# pilote.net
KiCad netlist of a schematic drawn in EAGLE
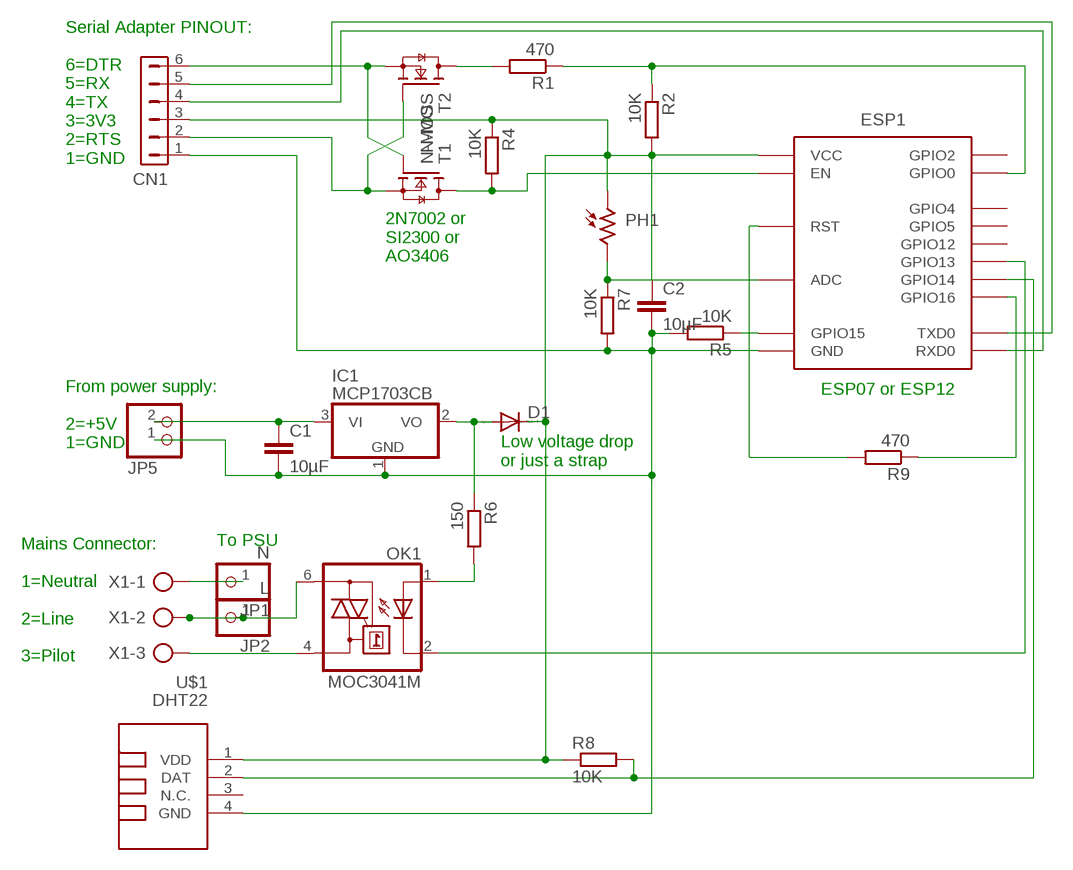
[diagram p0: schematic, sheet 1]

(export (version "E")
  (design (tool "Eeschema 10.0.6"))
  (components
    (comp (ref "C1")
      (value "10µF")
      (footprint "eagle-import:C1210")
      (libsource (lib "eagle-import") (part "C-EUC1210"))
    )
    (comp (ref "C2")
      (value "10µF")
      (footprint "eagle-import:C1210")
      (libsource (lib "eagle-import") (part "C-EUC1210"))
    )
    (comp (ref "CN1")
      (value "HDR-1X6-SIP-100")
      (footprint "eagle-import:SIP-100-6V")
      (libsource (lib "eagle-import") (part "HDR-1X6-SIP-100"))
    )
    (comp (ref "D1")
      (value "DIODE-SOD123")
      (footprint "eagle-import:SOD123")
      (libsource (lib "eagle-import") (part "DIODE-SOD123"))
    )
    (comp (ref "ESP1")
      (value "ESP8266-07THT")
      (footprint "eagle-import:ESP-07")
      (libsource (lib "eagle-import") (part "ESP8266-07THT"))
    )
    (comp (ref "IC1")
      (value "MCP1703CB")
      (footprint "eagle-import:SOT23")
      (libsource (lib "eagle-import") (part "MCP1703CB"))
    )
    (comp (ref "JP1")
      (value "N")
      (footprint "eagle-import:1X01")
      (libsource (lib "eagle-import") (part "PINHD-1X1"))
    )
    (comp (ref "JP2")
      (value "L")
      (footprint "eagle-import:1X01")
      (libsource (lib "eagle-import") (part "PINHD-1X1"))
    )
    (comp (ref "JP5")
      (value "PINHD-1X2")
      (footprint "eagle-import:1X02")
      (libsource (lib "eagle-import") (part "PINHD-1X2"))
    )
    (comp (ref "OK1")
      (value "MOC3041M")
      (footprint "eagle-import:DIL06")
      (libsource (lib "eagle-import") (part "MOC3041M"))
    )
    (comp (ref "PH1")
      (value "A1050_09")
      (footprint "eagle-import:T0-46-A10XX")
      (libsource (lib "eagle-import") (part "A1050_09"))
    )
    (comp (ref "R1")
      (value "470")
      (footprint "eagle-import:M0805")
      (libsource (lib "eagle-import") (part "R-EU_M0805"))
    )
    (comp (ref "R2")
      (value "10K")
      (footprint "eagle-import:M0805")
      (libsource (lib "eagle-import") (part "R-EU_M0805"))
    )
    (comp (ref "R4")
      (value "10K")
      (footprint "eagle-import:M0805")
      (libsource (lib "eagle-import") (part "R-EU_M0805"))
    )
    (comp (ref "R5")
      (value "10K")
      (footprint "eagle-import:M0805")
      (libsource (lib "eagle-import") (part "R-EU_M0805"))
    )
    (comp (ref "R6")
      (value "150")
      (footprint "eagle-import:M0805")
      (libsource (lib "eagle-import") (part "R-EU_M0805"))
    )
    (comp (ref "R7")
      (value "10K")
      (footprint "eagle-import:M0805")
      (libsource (lib "eagle-import") (part "R-EU_M0805"))
    )
    (comp (ref "R8")
      (value "10K")
      (footprint "eagle-import:M0805")
      (libsource (lib "eagle-import") (part "R-EU_M0805"))
    )
    (comp (ref "R9")
      (value "470")
      (footprint "eagle-import:M0805")
      (libsource (lib "eagle-import") (part "R-EU_M0805"))
    )
    (comp (ref "T1")
      (value "N-MOS")
      (footprint "eagle-import:SOT23")
      (libsource (lib "eagle-import") (part "2N7002E"))
    )
    (comp (ref "T2")
      (value "N-MOS")
      (footprint "eagle-import:SOT23")
      (libsource (lib "eagle-import") (part "2N7002E"))
    )
    (comp (ref "U$1")
      (value "DHT22")
      (footprint "eagle-import:TEMP-HUM-SENSOR-DHT22")
      (libsource (lib "eagle-import") (part "TEMP-HUM-SENSOR-DHT22"))
    )
    (comp (ref "X1")
      (value "AK500/3")
      (footprint "eagle-import:AK500_3")
      (libsource (lib "eagle-import") (part "AK500/3"))
    )
  )
  (nets
    (net (code "1") (name "Net-(ESP1-PadADC)") (class "Default")
      (node (ref "ESP1") (pin "ADC") (pinfunction "ADC_ADC") (pintype "input"))
      (node (ref "PH1") (pin "2") (pinfunction "2_2") (pintype "passive"))
      (node (ref "R7") (pin "1") (pinfunction "1_1") (pintype "passive"))
    )
    (net (code "2") (name "Net-(ESP1-PadGPIO0)") (class "Default")
      (node (ref "ESP1") (pin "GPIO0") (pinfunction "GPIO0_GPIO0") (pintype "bidirectional"))
      (node (ref "R1") (pin "1") (pinfunction "1_1") (pintype "passive"))
      (node (ref "R2") (pin "1") (pinfunction "1_1") (pintype "passive"))
    )
    (net (code "3") (name "Net-(ESP1-PadGPIO15)") (class "Default")
      (node (ref "ESP1") (pin "GPIO15") (pinfunction "GPIO15_GPIO15") (pintype "bidirectional"))
      (node (ref "R5") (pin "1") (pinfunction "1_1") (pintype "passive"))
    )
    (net (code "4") (name "Net-(ESP1-PadGPIO16)") (class "Default")
      (node (ref "ESP1") (pin "GPIO16") (pinfunction "GPIO16_GPIO16") (pintype "bidirectional"))
      (node (ref "R9") (pin "1") (pinfunction "1_1") (pintype "passive"))
    )
    (net (code "5") (name "Net-(ESP1-PadRST)") (class "Default")
      (node (ref "ESP1") (pin "RST") (pinfunction "RST_RST") (pintype "bidirectional"))
      (node (ref "R9") (pin "2") (pinfunction "2_2") (pintype "passive"))
    )
    (net (code "6") (name "Net-(ESP1-RXD0)") (class "Default")
      (node (ref "CN1") (pin "4") (pinfunction "4_4") (pintype "passive"))
      (node (ref "ESP1") (pin "RX") (pinfunction "RXD0_RX") (pintype "bidirectional"))
    )
    (net (code "7") (name "Net-(ESP1-TXD0)") (class "Default")
      (node (ref "CN1") (pin "5") (pinfunction "5_5") (pintype "passive"))
      (node (ref "ESP1") (pin "TX") (pinfunction "TXD0_TX") (pintype "bidirectional"))
    )
    (net (code "8") (name "Net-(IC1-GND)") (class "Default")
      (node (ref "C1") (pin "2") (pinfunction "2_2") (pintype "passive"))
      (node (ref "C2") (pin "2") (pinfunction "2_2") (pintype "passive"))
      (node (ref "CN1") (pin "1") (pinfunction "1_1") (pintype "passive"))
      (node (ref "ESP1") (pin "GND") (pinfunction "GND_GND") (pintype "bidirectional"))
      (node (ref "IC1") (pin "1") (pinfunction "GND_1") (pintype "passive"))
      (node (ref "JP5") (pin "1") (pinfunction "1_1") (pintype "passive"))
      (node (ref "R5") (pin "2") (pinfunction "2_2") (pintype "passive"))
      (node (ref "R7") (pin "2") (pinfunction "2_2") (pintype "passive"))
      (node (ref "U$1") (pin "4") (pinfunction "GND_4") (pintype "power_in"))
    )
    (net (code "9") (name "Net-(IC1-VI)") (class "Default")
      (node (ref "C1") (pin "1") (pinfunction "1_1") (pintype "passive"))
      (node (ref "IC1") (pin "3") (pinfunction "VI_3") (pintype "input"))
      (node (ref "JP5") (pin "2") (pinfunction "2_2") (pintype "passive"))
    )
    (net (code "10") (name "Net-(IC1-VO)") (class "Default")
      (node (ref "D1") (pin "A") (pinfunction "A_A") (pintype "passive"))
      (node (ref "IC1") (pin "2") (pinfunction "VO_2") (pintype "passive"))
      (node (ref "R6") (pin "1") (pinfunction "1_1") (pintype "passive"))
    )
    (net (code "11") (name "Net-(OK1-A)") (class "Default")
      (node (ref "OK1") (pin "1") (pinfunction "A_1") (pintype "passive"))
      (node (ref "R6") (pin "2") (pinfunction "2_2") (pintype "passive"))
    )
    (net (code "12") (name "Net-(OK1-A1)") (class "Default")
      (node (ref "OK1") (pin "4") (pinfunction "A1_4") (pintype "passive"))
      (node (ref "X1") (pin "3") (pinfunction "KL_3") (pintype "passive"))
    )
    (net (code "13") (name "Net-(OK1-A2)") (class "Default")
      (node (ref "JP2") (pin "1") (pinfunction "1_1") (pintype "passive"))
      (node (ref "OK1") (pin "6") (pinfunction "A2_6") (pintype "passive"))
      (node (ref "X1") (pin "2") (pinfunction "KL_2") (pintype "passive"))
    )
    (net (code "14") (name "Net-(OK1-C)") (class "Default")
      (node (ref "ESP1") (pin "GPIO13") (pinfunction "GPIO13_GPIO13") (pintype "bidirectional"))
      (node (ref "OK1") (pin "2") (pinfunction "C_2") (pintype "passive"))
    )
    (net (code "15") (name "Net-(T1-D)") (class "Default")
      (node (ref "R1") (pin "2") (pinfunction "2_2") (pintype "passive"))
      (node (ref "T1") (pin "3") (pinfunction "D_3") (pintype "passive"))
    )
    (net (code "16") (name "Net-(T1-G)") (class "Default")
      (node (ref "CN1") (pin "2") (pinfunction "2_2") (pintype "passive"))
      (node (ref "T1") (pin "1") (pinfunction "G_1") (pintype "passive"))
      (node (ref "T2") (pin "2") (pinfunction "S_2") (pintype "passive"))
    )
    (net (code "17") (name "Net-(T1-S)") (class "Default")
      (node (ref "CN1") (pin "6") (pinfunction "6_6") (pintype "passive"))
      (node (ref "T1") (pin "2") (pinfunction "S_2") (pintype "passive"))
      (node (ref "T2") (pin "1") (pinfunction "G_1") (pintype "passive"))
    )
    (net (code "18") (name "Net-(T2-D)") (class "Default")
      (node (ref "ESP1") (pin "EN") (pinfunction "EN_EN") (pintype "input"))
      (node (ref "R4") (pin "2") (pinfunction "2_2") (pintype "passive"))
      (node (ref "T2") (pin "3") (pinfunction "D_3") (pintype "passive"))
    )
    (net (code "19") (name "Net-(U$1-DAT)") (class "Default")
      (node (ref "ESP1") (pin "GPIO14") (pinfunction "GPIO14_GPIO14") (pintype "bidirectional"))
      (node (ref "R8") (pin "2") (pinfunction "2_2") (pintype "passive"))
      (node (ref "U$1") (pin "2") (pinfunction "DAT_2") (pintype "bidirectional"))
    )
    (net (code "20") (name "Net-(U$1-VDD)") (class "Default")
      (node (ref "C2") (pin "1") (pinfunction "1_1") (pintype "passive"))
      (node (ref "CN1") (pin "3") (pinfunction "3_3") (pintype "passive"))
      (node (ref "D1") (pin "C") (pinfunction "C_C") (pintype "passive"))
      (node (ref "ESP1") (pin "VCC") (pinfunction "VCC_VCC") (pintype "power_in"))
      (node (ref "PH1") (pin "1") (pinfunction "1_1") (pintype "passive"))
      (node (ref "R2") (pin "2") (pinfunction "2_2") (pintype "passive"))
      (node (ref "R4") (pin "1") (pinfunction "1_1") (pintype "passive"))
      (node (ref "R8") (pin "1") (pinfunction "1_1") (pintype "passive"))
      (node (ref "U$1") (pin "1") (pinfunction "VDD_1") (pintype "power_in"))
    )
    (net (code "21") (name "Net-(X1A-KL)") (class "Default")
      (node (ref "JP1") (pin "1") (pinfunction "1_1") (pintype "passive"))
      (node (ref "X1") (pin "1") (pinfunction "KL_1") (pintype "passive"))
    )
    (net (code "22") (name "unconnected-(ESP1-PadGPIO2)") (class "Default")
      (node (ref "ESP1") (pin "GPIO2") (pinfunction "GPIO2_GPIO2") (pintype "bidirectional"))
    )
    (net (code "23") (name "unconnected-(ESP1-PadGPIO4)") (class "Default")
      (node (ref "ESP1") (pin "GPIO4") (pinfunction "GPIO4_GPIO4") (pintype "bidirectional"))
    )
    (net (code "24") (name "unconnected-(ESP1-PadGPIO5)") (class "Default")
      (node (ref "ESP1") (pin "GPIO5") (pinfunction "GPIO5_GPIO5") (pintype "bidirectional"))
    )
    (net (code "25") (name "unconnected-(ESP1-PadGPIO12)") (class "Default")
      (node (ref "ESP1") (pin "GPIO12") (pinfunction "GPIO12_GPIO12") (pintype "bidirectional"))
    )
    (net (code "26") (name "unconnected-(U$1-N.C.-Pad3)") (class "Default")
      (node (ref "U$1") (pin "3") (pinfunction "N.C._3") (pintype "passive"))
    )
  )
)
